# WM-control_module_Rev1.net
KiCad netlist of a schematic drawn in EAGLE
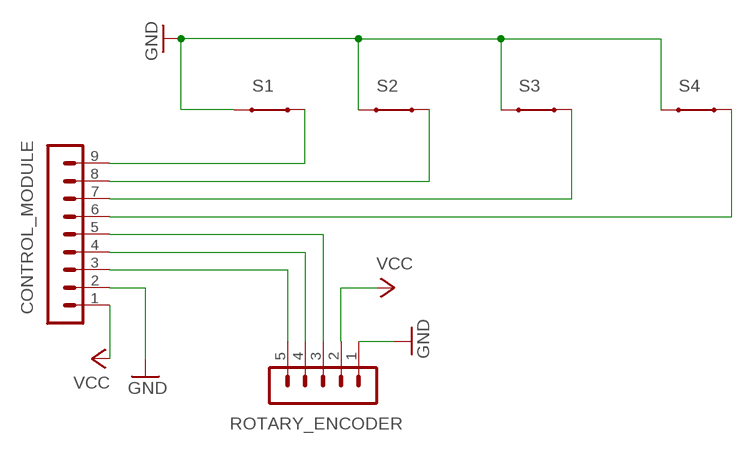
[diagram p0: schematic, sheet 1]

(export (version "E")
  (design (tool "Eeschema 10.0.6"))
  (components
    (comp (ref "CONTROL_MODULE")
      (value "MA09-1")
      (footprint "eagle-import:MA09-1")
      (libsource (lib "eagle-import") (part "MA09-1"))
    )
    (comp (ref "ROTARY_ENCODER")
      (value "MA05-1")
      (footprint "eagle-import:MA05-1")
      (libsource (lib "eagle-import") (part "MA05-1"))
    )
    (comp (ref "S1")
      (value "SWITCH-MOMENTARY-2-CLOSED")
      (footprint "eagle-import:TACTILE-PTH-12MM")
      (libsource (lib "eagle-import") (part "SWITCH-MOMENTARY-2-CLOSED"))
    )
    (comp (ref "S2")
      (value "SWITCH-MOMENTARY-2-CLOSED")
      (footprint "eagle-import:TACTILE-PTH-12MM")
      (libsource (lib "eagle-import") (part "SWITCH-MOMENTARY-2-CLOSED"))
    )
    (comp (ref "S3")
      (value "SWITCH-MOMENTARY-2-CLOSED")
      (footprint "eagle-import:TACTILE-PTH-12MM")
      (libsource (lib "eagle-import") (part "SWITCH-MOMENTARY-2-CLOSED"))
    )
    (comp (ref "S4")
      (value "SWITCH-MOMENTARY-2-CLOSED")
      (footprint "eagle-import:TACTILE-PTH-12MM")
      (libsource (lib "eagle-import") (part "SWITCH-MOMENTARY-2-CLOSED"))
    )
  )
  (nets
    (net (code "1") (name "GND") (class "Default")
      (node (ref "CONTROL_MODULE") (pin "2") (pinfunction "2_2") (pintype "passive"))
      (node (ref "ROTARY_ENCODER") (pin "1") (pinfunction "1_1") (pintype "passive"))
      (node (ref "S1") (pin "1") (pinfunction "1_1") (pintype "passive"))
      (node (ref "S2") (pin "1") (pinfunction "1_1") (pintype "passive"))
      (node (ref "S3") (pin "1") (pinfunction "1_1") (pintype "passive"))
      (node (ref "S4") (pin "1") (pinfunction "1_1") (pintype "passive"))
    )
    (net (code "2") (name "Net-(CONTROL_MODULE-Pad3)") (class "Default")
      (node (ref "CONTROL_MODULE") (pin "3") (pinfunction "3_3") (pintype "passive"))
      (node (ref "ROTARY_ENCODER") (pin "5") (pinfunction "5_5") (pintype "passive"))
    )
    (net (code "3") (name "Net-(CONTROL_MODULE-Pad4)") (class "Default")
      (node (ref "CONTROL_MODULE") (pin "4") (pinfunction "4_4") (pintype "passive"))
      (node (ref "ROTARY_ENCODER") (pin "4") (pinfunction "4_4") (pintype "passive"))
    )
    (net (code "4") (name "Net-(CONTROL_MODULE-Pad5)") (class "Default")
      (node (ref "CONTROL_MODULE") (pin "5") (pinfunction "5_5") (pintype "passive"))
      (node (ref "ROTARY_ENCODER") (pin "3") (pinfunction "3_3") (pintype "passive"))
    )
    (net (code "5") (name "Net-(S1-2)") (class "Default")
      (node (ref "CONTROL_MODULE") (pin "9") (pinfunction "9_9") (pintype "passive"))
      (node (ref "S1") (pin "3") (pinfunction "2_3") (pintype "passive"))
    )
    (net (code "6") (name "Net-(S2-2)") (class "Default")
      (node (ref "CONTROL_MODULE") (pin "8") (pinfunction "8_8") (pintype "passive"))
      (node (ref "S2") (pin "3") (pinfunction "2_3") (pintype "passive"))
    )
    (net (code "7") (name "Net-(S3-2)") (class "Default")
      (node (ref "CONTROL_MODULE") (pin "7") (pinfunction "7_7") (pintype "passive"))
      (node (ref "S3") (pin "3") (pinfunction "2_3") (pintype "passive"))
    )
    (net (code "8") (name "Net-(S4-2)") (class "Default")
      (node (ref "CONTROL_MODULE") (pin "6") (pinfunction "6_6") (pintype "passive"))
      (node (ref "S4") (pin "3") (pinfunction "2_3") (pintype "passive"))
    )
    (net (code "9") (name "VCC") (class "Default")
      (node (ref "CONTROL_MODULE") (pin "1") (pinfunction "1_1") (pintype "passive"))
      (node (ref "ROTARY_ENCODER") (pin "2") (pinfunction "2_2") (pintype "passive"))
    )
  )
)
